# pixracer_imu.net
KiCad netlist of a schematic drawn in Altium Designer
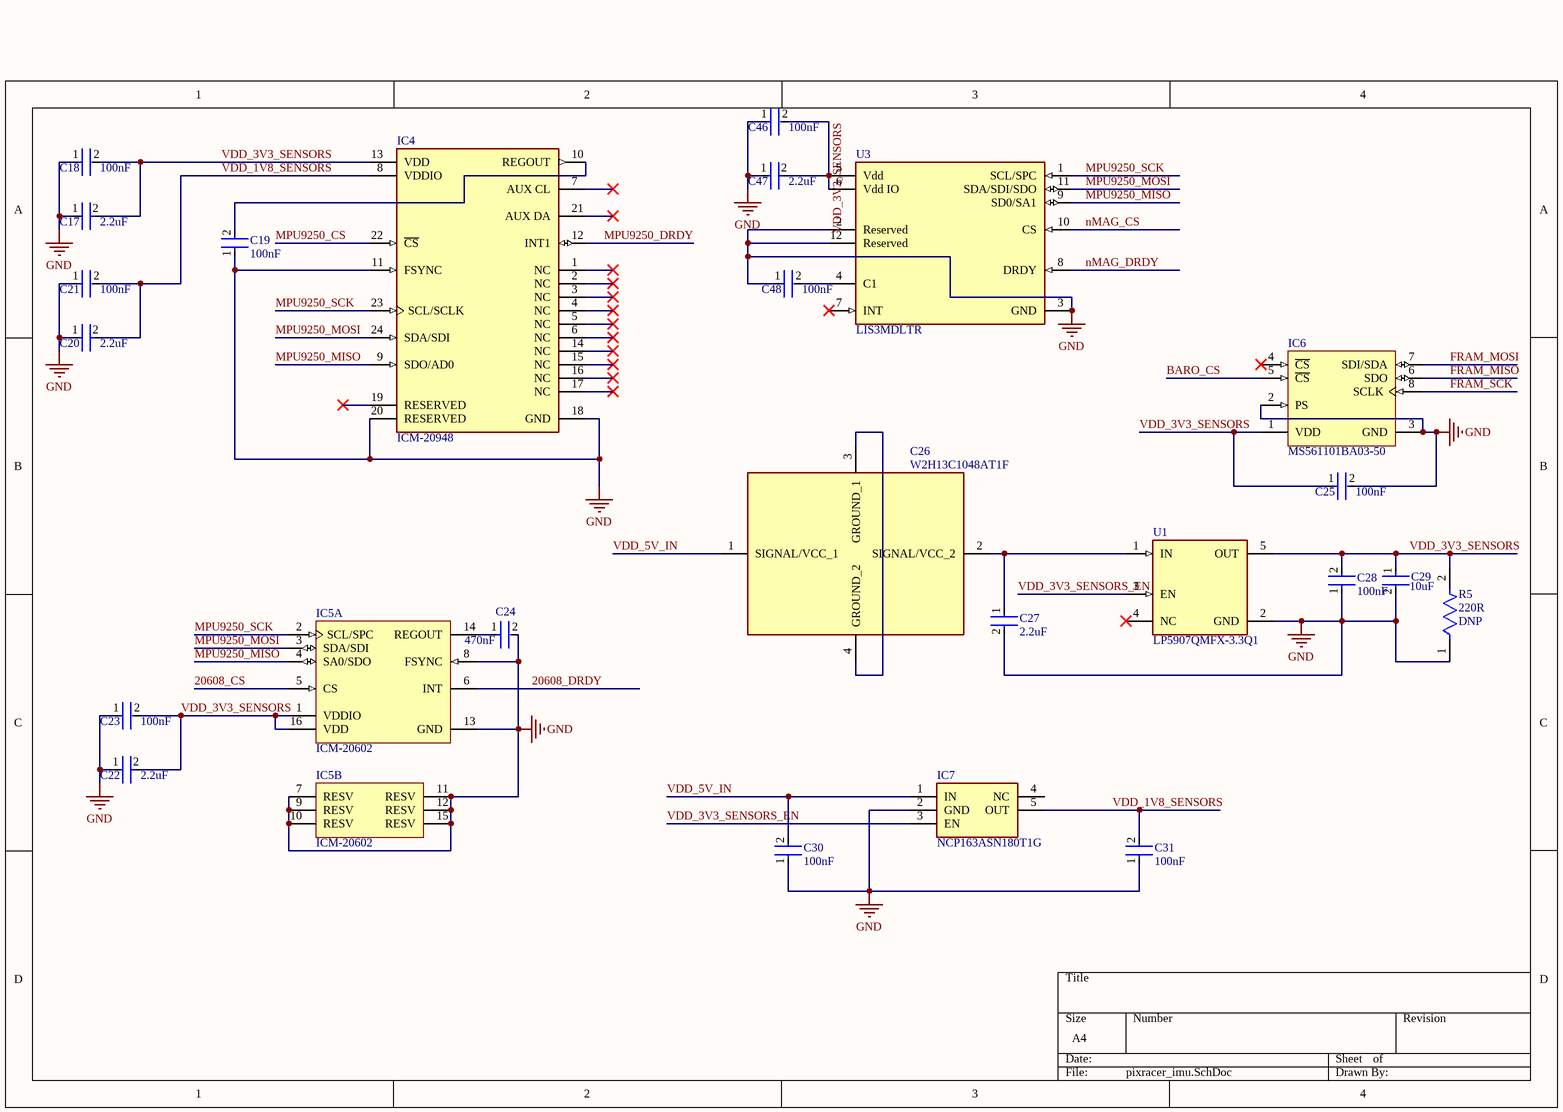
[diagram p0: pixracer_imu.SchDoc]

(export (version "E")
  (design (tool "Eeschema 10.0.6"))
  (components
    (comp (ref "C17")
      (value "C1608X7R1A225K080AC")
      (footprint "FP-C1608-080-0_1-MFG")
      (description "Multilayer Ceramic Capacitors 2.2μF ±10% 10V X7R SMD 0603")
      (fields (field (name "CAPACITANCE") "2.2uF") (field (name "TOLERANCE") "10%"))
      (libsource (lib "Altium Content Vault") (part "236180d848d6139a670b325ea6854c9"))
    )
    (comp (ref "C18")
      (value "0603ZC104MAT2A")
      (footprint "FP-0603-L_1_6_0_15-W_0_81-IPC_B")
      (description "General Purpose Ceramic Capacitor, 0603, 100nF, 20%, X7R, 15%, 10V")
      (fields (field (name "TOLERANCE") "20%") (field (name "CAPACITANCE") "100nF"))
      (libsource (lib "Altium Content Vault") (part "02cd4be3c70576c341d710602a673aa"))
    )
    (comp (ref "C19")
      (value "0603ZC104MAT2A")
      (footprint "FP-0603-L_1_6_0_15-W_0_81-IPC_B")
      (description "General Purpose Ceramic Capacitor, 0603, 100nF, 20%, X7R, 15%, 10V")
      (fields (field (name "TOLERANCE") "20%") (field (name "CAPACITANCE") "100nF"))
      (libsource (lib "Altium Content Vault") (part "02cd4be3c70576c341d710602a673aa"))
    )
    (comp (ref "C20")
      (value "C1608X7R1A225K080AC")
      (footprint "FP-C1608-080-0_1-MFG")
      (description "Multilayer Ceramic Capacitors 2.2μF ±10% 10V X7R SMD 0603")
      (fields (field (name "CAPACITANCE") "2.2uF") (field (name "TOLERANCE") "10%"))
      (libsource (lib "Altium Content Vault") (part "236180d848d6139a670b325ea6854c9"))
    )
    (comp (ref "C21")
      (value "0603ZC104MAT2A")
      (footprint "FP-0603-L_1_6_0_15-W_0_81-IPC_B")
      (description "General Purpose Ceramic Capacitor, 0603, 100nF, 20%, X7R, 15%, 10V")
      (fields (field (name "TOLERANCE") "20%") (field (name "CAPACITANCE") "100nF"))
      (libsource (lib "Altium Content Vault") (part "02cd4be3c70576c341d710602a673aa"))
    )
    (comp (ref "C22")
      (value "C1608X7R1A225K080AC")
      (footprint "FP-C1608-080-0_1-MFG")
      (description "Multilayer Ceramic Capacitors 2.2μF ±10% 10V X7R SMD 0603")
      (fields (field (name "CAPACITANCE") "2.2uF") (field (name "TOLERANCE") "10%"))
      (libsource (lib "Altium Content Vault") (part "236180d848d6139a670b325ea6854c9"))
    )
    (comp (ref "C23")
      (value "0603ZC104MAT2A")
      (footprint "FP-0603-L_1_6_0_15-W_0_81-IPC_B")
      (description "General Purpose Ceramic Capacitor, 0603, 100nF, 20%, X7R, 15%, 10V")
      (fields (field (name "TOLERANCE") "20%") (field (name "CAPACITANCE") "100nF"))
      (libsource (lib "Altium Content Vault") (part "02cd4be3c70576c341d710602a673aa"))
    )
    (comp (ref "C24")
      (value "CL10B474KP8NNNC")
      (footprint "FP-CL10-IPC_B")
      (description "Cap Ceramic 470nF 10V X7R ±10% Pad SMD 0603 +125°C T/R")
      (fields
        (field (name "VOLTAGE") "10V")
        (field (name "CAPACITANCE") "470nF")
        (field (name "TOLERANCE") "10%")
      )
      (libsource (lib "Altium Content Vault") (part "b4654b650e69147ec39a6b967a45e02"))
    )
    (comp (ref "C25")
      (value "0603ZC104MAT2A")
      (footprint "FP-0603-L_1_6_0_15-W_0_81-IPC_B")
      (description "General Purpose Ceramic Capacitor, 0603, 100nF, 20%, X7R, 15%, 10V")
      (fields (field (name "TOLERANCE") "20%") (field (name "CAPACITANCE") "100nF"))
      (libsource (lib "Altium Content Vault") (part "02cd4be3c70576c341d710602a673aa"))
    )
    (comp (ref "C26")
      (value "W2H13C1048AT1F")
      (footprint "SamacSys:W2H13C1048AT1A")
      (description "Capacitor")
      (fields (field (name "MOUSER PART NUMBER") "581-W2H13C1048AT1F"))
      (libsource (lib "*") (part "W2H13C1048AT1F"))
    )
    (comp (ref "C27")
      (value "C1608X7R1A225K080AC")
      (footprint "FP-C1608-080-0_1-MFG")
      (description "Multilayer Ceramic Capacitors 2.2μF ±10% 10V X7R SMD 0603")
      (fields (field (name "CAPACITANCE") "2.2uF") (field (name "TOLERANCE") "10%"))
      (libsource (lib "Altium Content Vault") (part "236180d848d6139a670b325ea6854c9"))
    )
    (comp (ref "C28")
      (value "0603ZC104MAT2A")
      (footprint "FP-0603-L_1_6_0_15-W_0_81-IPC_B")
      (description "General Purpose Ceramic Capacitor, 0603, 100nF, 20%, X7R, 15%, 10V")
      (fields (field (name "TOLERANCE") "20%") (field (name "CAPACITANCE") "100nF"))
      (libsource (lib "Altium Content Vault") (part "02cd4be3c70576c341d710602a673aa"))
    )
    (comp (ref "C29")
      (value "CL10A106KP8NNND")
      (footprint "FP-CL10-IPC_B")
      (description "Cap Ceramic 10uF 10V X5R ±10% Pad SMD 0603 +85°C T/R")
      (fields (field (name "TOLERANCE") "10%") (field (name "CAPACITANCE") "10uF"))
      (libsource (lib "Altium Content Vault") (part "b4654b650e69147ec39a6b967a45e02"))
    )
    (comp (ref "C30")
      (value "0603ZC104MAT2A")
      (footprint "FP-0603-L_1_6_0_15-W_0_81-IPC_B")
      (description "General Purpose Ceramic Capacitor, 0603, 100nF, 20%, X7R, 15%, 10V")
      (fields (field (name "TOLERANCE") "20%") (field (name "CAPACITANCE") "100nF"))
      (libsource (lib "Altium Content Vault") (part "02cd4be3c70576c341d710602a673aa"))
    )
    (comp (ref "C31")
      (value "0603ZC104MAT2A")
      (footprint "FP-0603-L_1_6_0_15-W_0_81-IPC_B")
      (description "General Purpose Ceramic Capacitor, 0603, 100nF, 20%, X7R, 15%, 10V")
      (fields (field (name "TOLERANCE") "20%") (field (name "CAPACITANCE") "100nF"))
      (libsource (lib "Altium Content Vault") (part "02cd4be3c70576c341d710602a673aa"))
    )
    (comp (ref "C46")
      (value "0603ZC104MAT2A")
      (footprint "FP-0603-L_1_6_0_15-W_0_81-IPC_B")
      (description "General Purpose Ceramic Capacitor, 0603, 100nF, 20%, X7R, 15%, 10V")
      (fields (field (name "TOLERANCE") "20%") (field (name "CAPACITANCE") "100nF"))
      (libsource (lib "Altium Content Vault") (part "02cd4be3c70576c341d710602a673aa"))
    )
    (comp (ref "C47")
      (value "C1608X7R1A225K080AC")
      (footprint "FP-C1608-080-0_1-MFG")
      (description "Multilayer Ceramic Capacitors 2.2μF ±10% 10V X7R SMD 0603")
      (fields (field (name "CAPACITANCE") "2.2uF") (field (name "TOLERANCE") "10%"))
      (libsource (lib "Altium Content Vault") (part "236180d848d6139a670b325ea6854c9"))
    )
    (comp (ref "C48")
      (value "0603ZC104MAT2A")
      (footprint "FP-0603-L_1_6_0_15-W_0_81-IPC_B")
      (description "General Purpose Ceramic Capacitor, 0603, 100nF, 20%, X7R, 15%, 10V")
      (fields (field (name "TOLERANCE") "20%") (field (name "CAPACITANCE") "100nF"))
      (libsource (lib "Altium Content Vault") (part "02cd4be3c70576c341d710602a673aa"))
    )
    (comp (ref "IC4")
      (value "ICM-20948")
      (footprint "FP-ICM-20948-IPC_C")
      (description "IMU ACCEL/GYRO/COMPI2C/SPI 24QFN")
      (libsource (lib "Altium Content Vault") (part "f55aed9b0ea5cc58222276bed130340"))
    )
    (comp (ref "IC5")
      (value "ICM-20602")
      (footprint "INSE-I62-16")
      (fields (field (name "MANUFACTURER") "InvenSense"))
      (libsource (lib "Altium Content Vault") (part "INSE-ICM-20602-16"))
    )
    (comp (ref "IC6")
      (value "MS561101BA03-50")
      (footprint "MSI-MS561101BA03-50-8_V")
      (fields (field (name "MANUFACTURER") "Measurement Specialties"))
      (libsource (lib "Altium Content Vault") (part "MSI-MS561101BA03-50-8"))
    )
    (comp (ref "IC7")
      (value "NCP163ASN180T1G")
      (footprint "SamacSys:SOT95P280X145-5N")
      (description "Integrated Circuit")
      (fields (field (name "MOUSER PART NUMBER") "863-NCP163ASN180T1G"))
      (libsource (lib "*") (part "NCP163ASN180T1G"))
    )
    (comp (ref "R5")
      (value "DNP")
      (footprint "FP-CRCW0603-e3-MFG")
      (description "RES Thick Film, 220Ω, 1%, 0.1W, 100ppm/°C, 0603")
      (fields (field (name "TOLERANCE") "1%") (field (name "RESISTANCE") "220R"))
      (libsource (lib "Altium Content Vault") (part "1029c3af85768c4190bb7ad29bc67b5"))
    )
    (comp (ref "U1")
      (value "LP5907QMFX-3.3Q1")
      (footprint "FP-DBV0005A-MFG")
      (description "IC REG LINEAR 3.3V 250MA SOT23-5")
      (fields
        (field (name "MANUFACTURER") "Texas Instruments")
        (field (name "OCTOPART") "https://octopart.com/lp5907qmfx-3.3q1-texas+instruments-50417899")
      )
      (libsource (lib "Altium Content Vault") (part "e6eddeb8bab6a4ee265087e5808ab9f"))
    )
    (comp (ref "U3")
      (value "LIS3MDLTR")
      (footprint "FP-VFLGA-12-8365767-MFG")
      (description "SENSOR MR I2C/SPI 12LGA")
      (fields
        (field (name "OCTOPART") "https://octopart.com/lis3mdltr-stmicroelectronics-29403125")
        (field (name "MANUFACTURER") "STMicroelectronics")
      )
      (libsource (lib "Altium Content Vault") (part "41c0331d4207a07573b21020ef49d7d"))
    )
  )
  (nets
    (net (code "1") (name "/20608_CS") (class "Default")
      (node (ref "IC5") (pin "5") (pinfunction "CS_5") (pintype "input"))
    )
    (net (code "2") (name "/20608_DRDY") (class "Default")
      (node (ref "IC5") (pin "6") (pinfunction "INT_6") (pintype "open_collector"))
    )
    (net (code "3") (name "/BARO_CS") (class "Default")
      (node (ref "IC6") (pin "5") (pinfunction "~{CS}_5") (pintype "input"))
    )
    (net (code "4") (name "/FRAM_MISO") (class "Default")
      (node (ref "IC6") (pin "6") (pinfunction "SDO_6") (pintype "bidirectional"))
    )
    (net (code "5") (name "/FRAM_MOSI") (class "Default")
      (node (ref "IC6") (pin "7") (pinfunction "SDI/SDA_7") (pintype "bidirectional"))
    )
    (net (code "6") (name "/FRAM_SCK") (class "Default")
      (node (ref "IC6") (pin "8") (pinfunction "SCLK_8") (pintype "input"))
    )
    (net (code "7") (name "/MPU9250_CS") (class "Default")
      (node (ref "IC4") (pin "22") (pinfunction "~{CS}_22") (pintype "input"))
    )
    (net (code "8") (name "/MPU9250_DRDY") (class "Default")
      (node (ref "IC4") (pin "12") (pinfunction "INT1_12") (pintype "bidirectional"))
    )
    (net (code "9") (name "/MPU9250_MISO") (class "Default")
      (node (ref "IC4") (pin "9") (pinfunction "SDO/AD0_9") (pintype "input"))
      (node (ref "IC5") (pin "4") (pinfunction "SA0/SDO_4") (pintype "bidirectional"))
      (node (ref "U3") (pin "9") (pinfunction "SD0/SA1_9") (pintype "bidirectional"))
    )
    (net (code "10") (name "/MPU9250_MOSI") (class "Default")
      (node (ref "IC4") (pin "24") (pinfunction "SDA/SDI_24") (pintype "input"))
      (node (ref "IC5") (pin "3") (pinfunction "SDA/SDI_3") (pintype "bidirectional"))
      (node (ref "U3") (pin "11") (pinfunction "SDA/SDI/SDO_11") (pintype "bidirectional"))
    )
    (net (code "11") (name "/MPU9250_SCK") (class "Default")
      (node (ref "IC4") (pin "23") (pinfunction "SCL/SCLK_23") (pintype "input"))
      (node (ref "IC5") (pin "2") (pinfunction "SCL/SPC_2") (pintype "input"))
      (node (ref "U3") (pin "1") (pinfunction "SCL/SPC_1") (pintype "input"))
    )
    (net (code "12") (name "/VDD_1V8_SENSORS") (class "Default")
      (node (ref "C20") (pin "2") (pinfunction "2_2") (pintype "passive"))
      (node (ref "C21") (pin "2") (pinfunction "2_2") (pintype "passive"))
      (node (ref "C31") (pin "2") (pinfunction "2_2") (pintype "passive"))
      (node (ref "IC4") (pin "8") (pinfunction "VDDIO_8") (pintype "power_in"))
      (node (ref "IC7") (pin "5") (pinfunction "OUT_5") (pintype "passive"))
    )
    (net (code "13") (name "/VDD_3V3_SENSORS") (class "Default")
      (node (ref "C17") (pin "2") (pinfunction "2_2") (pintype "passive"))
      (node (ref "C18") (pin "2") (pinfunction "2_2") (pintype "passive"))
      (node (ref "C22") (pin "2") (pinfunction "2_2") (pintype "passive"))
      (node (ref "C23") (pin "2") (pinfunction "2_2") (pintype "passive"))
      (node (ref "C25") (pin "1") (pinfunction "1_1") (pintype "passive"))
      (node (ref "C28") (pin "2") (pinfunction "2_2") (pintype "passive"))
      (node (ref "C29") (pin "1") (pinfunction "1_1") (pintype "passive"))
      (node (ref "C46") (pin "2") (pinfunction "2_2") (pintype "passive"))
      (node (ref "C47") (pin "2") (pinfunction "2_2") (pintype "passive"))
      (node (ref "IC4") (pin "13") (pinfunction "VDD_13") (pintype "power_in"))
      (node (ref "IC5") (pin "1") (pinfunction "VDDIO_1") (pintype "power_in"))
      (node (ref "IC5") (pin "16") (pinfunction "VDD_16") (pintype "power_in"))
      (node (ref "IC6") (pin "1") (pinfunction "VDD_1") (pintype "power_in"))
      (node (ref "R5") (pin "2") (pinfunction "2_2") (pintype "passive"))
      (node (ref "U1") (pin "5") (pinfunction "OUT_5") (pintype "power_in"))
      (node (ref "U3") (pin "5") (pinfunction "Vdd_5") (pintype "power_in"))
      (node (ref "U3") (pin "6") (pinfunction "Vdd_IO_6") (pintype "power_in"))
    )
    (net (code "14") (name "/VDD_3V3_SENSORS_EN") (class "Default")
      (node (ref "IC7") (pin "3") (pinfunction "EN_3") (pintype "passive"))
      (node (ref "U1") (pin "3") (pinfunction "EN_3") (pintype "input"))
    )
    (net (code "15") (name "/VDD_5V_IN") (class "Default")
      (node (ref "C26") (pin "1") (pinfunction "SIGNAL/VCC_1_1") (pintype "passive"))
      (node (ref "C30") (pin "2") (pinfunction "2_2") (pintype "passive"))
      (node (ref "IC7") (pin "1") (pinfunction "IN_1") (pintype "passive"))
    )
    (net (code "16") (name "/nMAG_CS") (class "Default")
      (node (ref "U3") (pin "10") (pinfunction "CS_10") (pintype "input"))
    )
    (net (code "17") (name "/nMAG_DRDY") (class "Default")
      (node (ref "U3") (pin "8") (pinfunction "DRDY_8") (pintype "input"))
    )
    (net (code "18") (name "GND") (class "Default")
      (node (ref "C17") (pin "1") (pinfunction "1_1") (pintype "passive"))
      (node (ref "C18") (pin "1") (pinfunction "1_1") (pintype "passive"))
      (node (ref "C19") (pin "1") (pinfunction "1_1") (pintype "passive"))
      (node (ref "C20") (pin "1") (pinfunction "1_1") (pintype "passive"))
      (node (ref "C21") (pin "1") (pinfunction "1_1") (pintype "passive"))
      (node (ref "C22") (pin "1") (pinfunction "1_1") (pintype "passive"))
      (node (ref "C23") (pin "1") (pinfunction "1_1") (pintype "passive"))
      (node (ref "C24") (pin "2") (pinfunction "2_2") (pintype "passive"))
      (node (ref "C25") (pin "2") (pinfunction "2_2") (pintype "passive"))
      (node (ref "C27") (pin "2") (pinfunction "2_2") (pintype "passive"))
      (node (ref "C28") (pin "1") (pinfunction "1_1") (pintype "passive"))
      (node (ref "C29") (pin "2") (pinfunction "2_2") (pintype "passive"))
      (node (ref "C30") (pin "1") (pinfunction "1_1") (pintype "passive"))
      (node (ref "C31") (pin "1") (pinfunction "1_1") (pintype "passive"))
      (node (ref "C46") (pin "1") (pinfunction "1_1") (pintype "passive"))
      (node (ref "C47") (pin "1") (pinfunction "1_1") (pintype "passive"))
      (node (ref "C48") (pin "1") (pinfunction "1_1") (pintype "passive"))
      (node (ref "IC4") (pin "11") (pinfunction "FSYNC_11") (pintype "input"))
      (node (ref "IC4") (pin "18") (pinfunction "GND_18") (pintype "power_in"))
      (node (ref "IC4") (pin "20") (pinfunction "RESERVED_20") (pintype "passive"))
      (node (ref "IC5") (pin "10") (pinfunction "RESV_10") (pintype "passive"))
      (node (ref "IC5") (pin "11") (pinfunction "RESV_11") (pintype "passive"))
      (node (ref "IC5") (pin "12") (pinfunction "RESV_12") (pintype "passive"))
      (node (ref "IC5") (pin "13") (pinfunction "GND_13") (pintype "power_in"))
      (node (ref "IC5") (pin "15") (pinfunction "RESV_15") (pintype "passive"))
      (node (ref "IC5") (pin "7") (pinfunction "RESV_7") (pintype "passive"))
      (node (ref "IC5") (pin "8") (pinfunction "FSYNC_8") (pintype "input"))
      (node (ref "IC5") (pin "9") (pinfunction "RESV_9") (pintype "passive"))
      (node (ref "IC6") (pin "2") (pinfunction "PS_2") (pintype "input"))
      (node (ref "IC6") (pin "3") (pinfunction "GND_3") (pintype "power_in"))
      (node (ref "IC7") (pin "2") (pinfunction "GND_2") (pintype "passive"))
      (node (ref "R5") (pin "1") (pinfunction "1_1") (pintype "passive"))
      (node (ref "U1") (pin "2") (pinfunction "GND_2") (pintype "power_in"))
      (node (ref "U3") (pin "12") (pinfunction "Reserved_12") (pintype "passive"))
      (node (ref "U3") (pin "2") (pinfunction "Reserved_2") (pintype "passive"))
      (node (ref "U3") (pin "3") (pinfunction "GND_3") (pintype "power_in"))
    )
    (net (code "19") (name "Net-(C26-GROUND_1)") (class "Default")
      (node (ref "C26") (pin "3") (pinfunction "GROUND_1_3") (pintype "passive"))
      (node (ref "C26") (pin "4") (pinfunction "GROUND_2_4") (pintype "passive"))
    )
    (net (code "20") (name "Net-(C26-SIGNAL{slash}VCC_2)") (class "Default")
      (node (ref "C26") (pin "2") (pinfunction "SIGNAL/VCC_2_2") (pintype "passive"))
      (node (ref "C27") (pin "1") (pinfunction "1_1") (pintype "passive"))
      (node (ref "U1") (pin "1") (pinfunction "IN_1") (pintype "input"))
    )
    (net (code "21") (name "Net-(IC4-REGOUT)") (class "Default")
      (node (ref "C19") (pin "2") (pinfunction "2_2") (pintype "passive"))
      (node (ref "IC4") (pin "10") (pinfunction "REGOUT_10") (pintype "output"))
    )
    (net (code "22") (name "Net-(IC5A-REGOUT)") (class "Default")
      (node (ref "C24") (pin "1") (pinfunction "1_1") (pintype "passive"))
      (node (ref "IC5") (pin "14") (pinfunction "REGOUT_14") (pintype "passive"))
    )
    (net (code "23") (name "Net-(U3-C1)") (class "Default")
      (node (ref "C48") (pin "2") (pinfunction "2_2") (pintype "passive"))
      (node (ref "U3") (pin "4") (pinfunction "C1_4") (pintype "passive"))
    )
    (net (code "24") (name "unconnected-(IC4-AUX_CL-Pad7)") (class "Default")
      (node (ref "IC4") (pin "7") (pinfunction "AUX_CL_7") (pintype "passive+no_connect"))
    )
    (net (code "25") (name "unconnected-(IC4-AUX_DA-Pad21)") (class "Default")
      (node (ref "IC4") (pin "21") (pinfunction "AUX_DA_21") (pintype "passive+no_connect"))
    )
    (net (code "26") (name "unconnected-(IC4-NC-Pad1)") (class "Default")
      (node (ref "IC4") (pin "1") (pinfunction "NC_1") (pintype "passive+no_connect"))
    )
    (net (code "27") (name "unconnected-(IC4-NC-Pad2)") (class "Default")
      (node (ref "IC4") (pin "2") (pinfunction "NC_2") (pintype "passive+no_connect"))
    )
    (net (code "28") (name "unconnected-(IC4-NC-Pad3)") (class "Default")
      (node (ref "IC4") (pin "3") (pinfunction "NC_3") (pintype "passive+no_connect"))
    )
    (net (code "29") (name "unconnected-(IC4-NC-Pad4)") (class "Default")
      (node (ref "IC4") (pin "4") (pinfunction "NC_4") (pintype "passive+no_connect"))
    )
    (net (code "30") (name "unconnected-(IC4-NC-Pad5)") (class "Default")
      (node (ref "IC4") (pin "5") (pinfunction "NC_5") (pintype "passive+no_connect"))
    )
    (net (code "31") (name "unconnected-(IC4-NC-Pad6)") (class "Default")
      (node (ref "IC4") (pin "6") (pinfunction "NC_6") (pintype "passive+no_connect"))
    )
    (net (code "32") (name "unconnected-(IC4-NC-Pad14)") (class "Default")
      (node (ref "IC4") (pin "14") (pinfunction "NC_14") (pintype "passive+no_connect"))
    )
    (net (code "33") (name "unconnected-(IC4-NC-Pad15)") (class "Default")
      (node (ref "IC4") (pin "15") (pinfunction "NC_15") (pintype "passive+no_connect"))
    )
    (net (code "34") (name "unconnected-(IC4-NC-Pad16)") (class "Default")
      (node (ref "IC4") (pin "16") (pinfunction "NC_16") (pintype "passive+no_connect"))
    )
    (net (code "35") (name "unconnected-(IC4-NC-Pad17)") (class "Default")
      (node (ref "IC4") (pin "17") (pinfunction "NC_17") (pintype "passive+no_connect"))
    )
    (net (code "36") (name "unconnected-(IC4-RESERVED-Pad19)") (class "Default")
      (node (ref "IC4") (pin "19") (pinfunction "RESERVED_19") (pintype "passive+no_connect"))
    )
    (net (code "37") (name "unconnected-(IC6-~{CS}-Pad4)") (class "Default")
      (node (ref "IC6") (pin "4") (pinfunction "~{CS}_4") (pintype "input+no_connect"))
    )
    (net (code "38") (name "unconnected-(IC7-NC-Pad4)") (class "Default")
      (node (ref "IC7") (pin "4") (pinfunction "NC_4") (pintype "passive"))
    )
    (net (code "39") (name "unconnected-(U1-NC-Pad4)") (class "Default")
      (node (ref "U1") (pin "4") (pinfunction "NC_4") (pintype "passive+no_connect"))
    )
    (net (code "40") (name "unconnected-(U3-INT-Pad7)") (class "Default")
      (node (ref "U3") (pin "7") (pinfunction "INT_7") (pintype "input+no_connect"))
    )
  )
)
